# SoftStart_V2_0.net
KiCad netlist of a schematic drawn in EAGLE
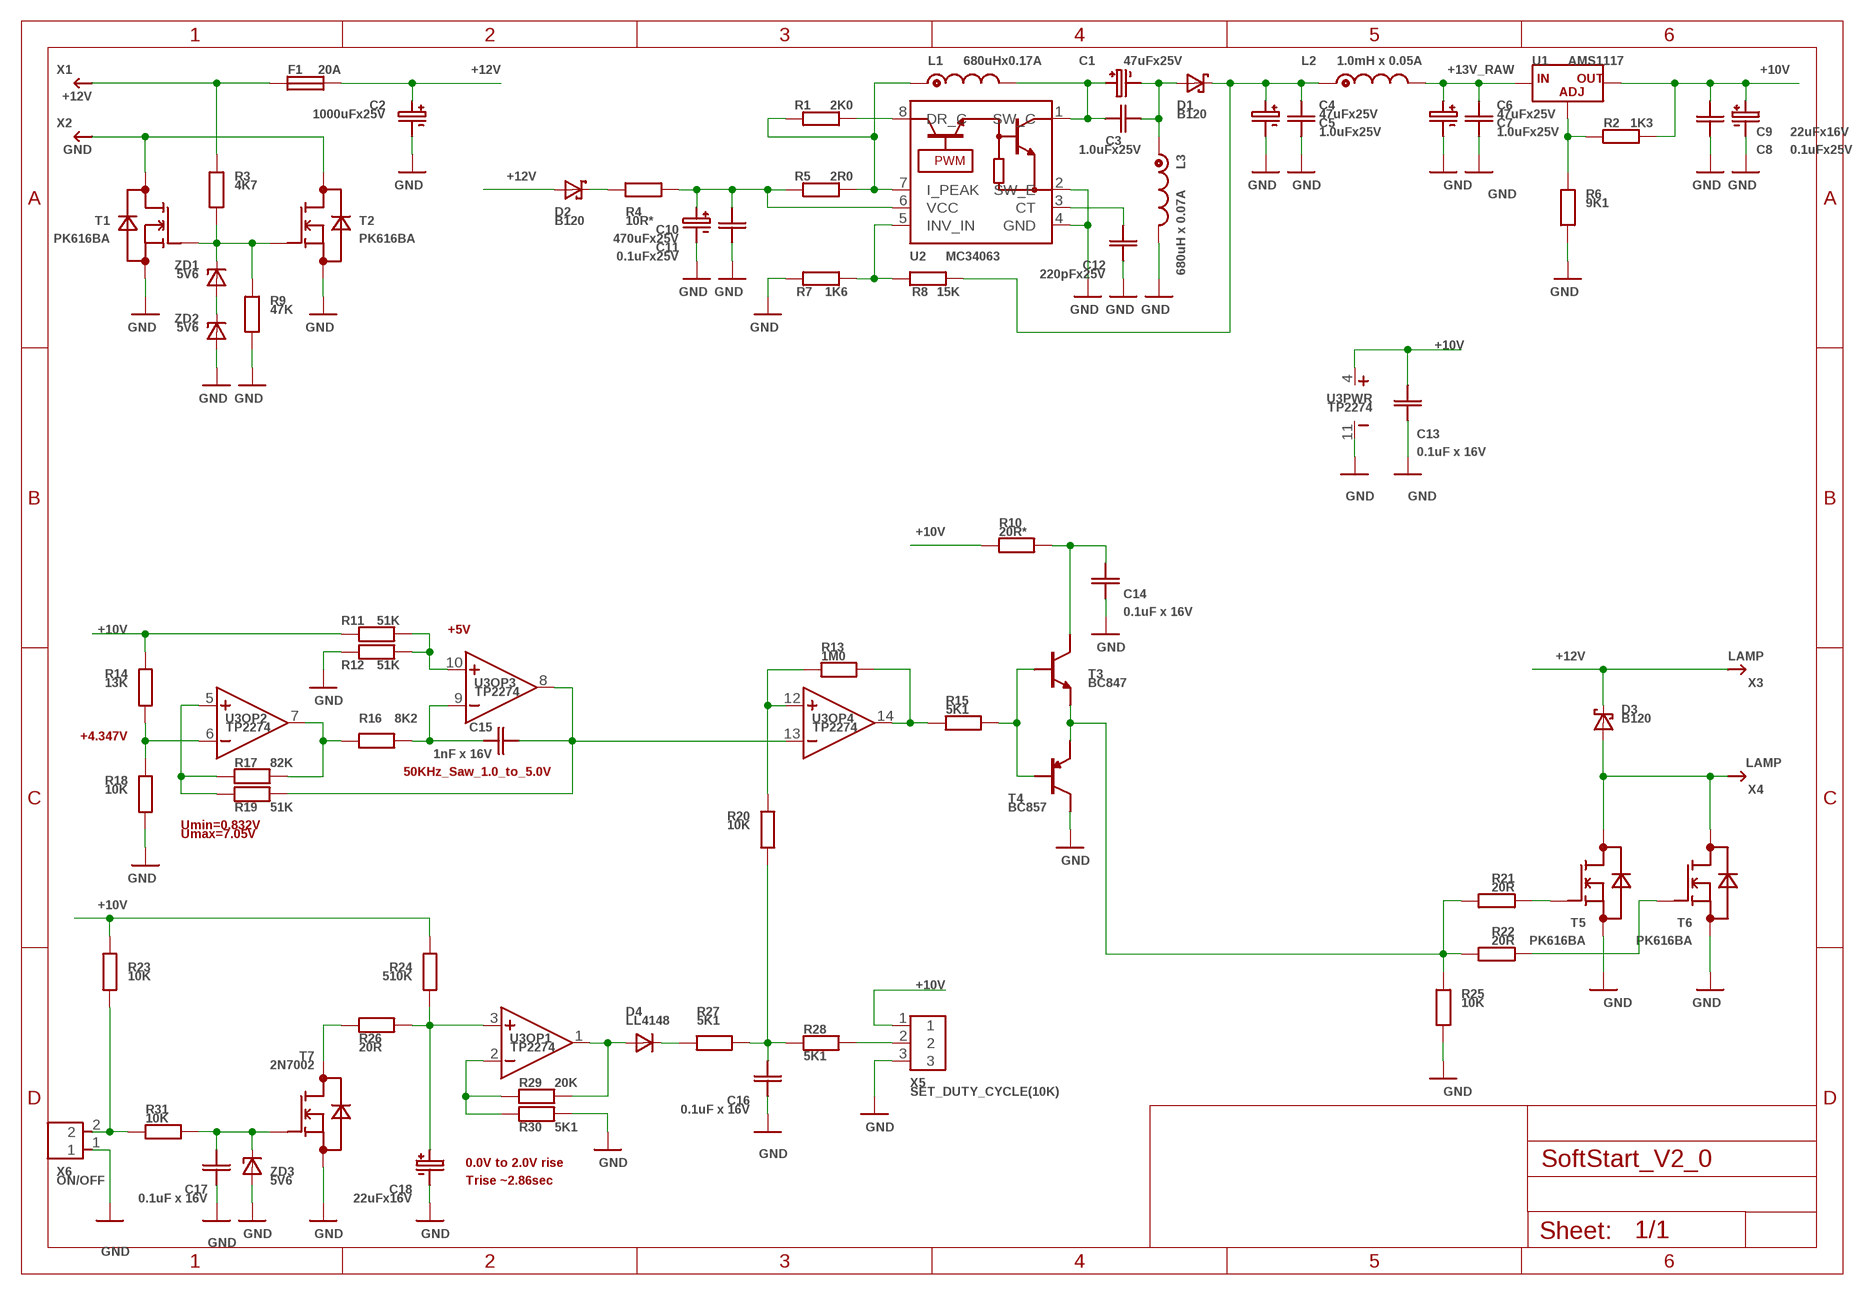
[diagram p0: schematic, sheet 1]

(export (version "E")
  (design (tool "Eeschema 10.0.6"))
  (components
    (comp (ref "C1")
      (value "47uFx25V")
      (footprint "eagle-import:CE_6.3MM")
      (libsource (lib "eagle-import") (part "CE6.3MM"))
    )
    (comp (ref "C2")
      (value "1000uFx25V")
      (footprint "eagle-import:CE_10MM")
      (libsource (lib "eagle-import") (part "CE10MM"))
    )
    (comp (ref "C3")
      (value "1.0uFx25V")
      (footprint "eagle-import:RSMD_1206")
      (libsource (lib "eagle-import") (part "CSMD_1206"))
    )
    (comp (ref "C4")
      (value "47uFx25V")
      (footprint "eagle-import:CE_6.3MM")
      (libsource (lib "eagle-import") (part "CE6.3MM"))
    )
    (comp (ref "C5")
      (value "1.0uFx25V")
      (footprint "eagle-import:RSMD_1206")
      (libsource (lib "eagle-import") (part "CSMD_1206"))
    )
    (comp (ref "C6")
      (value "47uFx25V")
      (footprint "eagle-import:CE_6.3MM")
      (libsource (lib "eagle-import") (part "CE6.3MM"))
    )
    (comp (ref "C7")
      (value "1.0uFx25V")
      (footprint "eagle-import:RSMD_1206")
      (libsource (lib "eagle-import") (part "CSMD_1206"))
    )
    (comp (ref "C8")
      (value "0.1uFx25V")
      (footprint "eagle-import:RSMD_0805")
      (libsource (lib "eagle-import") (part "CSMD_0805"))
    )
    (comp (ref "C9")
      (value "22uFx16V")
      (footprint "eagle-import:CE_6.3MM")
      (libsource (lib "eagle-import") (part "CE6.3MM"))
    )
    (comp (ref "C10")
      (value "470uFx25V")
      (footprint "eagle-import:CE_10MM")
      (libsource (lib "eagle-import") (part "CE10MM"))
    )
    (comp (ref "C11")
      (value "0.1uFx25V")
      (footprint "eagle-import:RSMD_1206")
      (libsource (lib "eagle-import") (part "CSMD_1206"))
    )
    (comp (ref "C12")
      (value "220pFx25V")
      (footprint "eagle-import:RSMD_0805")
      (libsource (lib "eagle-import") (part "CSMD_0805"))
    )
    (comp (ref "C13")
      (value "0.1uF x 16V")
      (footprint "eagle-import:RSMD_0805")
      (libsource (lib "eagle-import") (part "CSMD_0805"))
    )
    (comp (ref "C14")
      (value "0.1uF x 16V")
      (footprint "eagle-import:RSMD_0805")
      (libsource (lib "eagle-import") (part "CSMD_0805"))
    )
    (comp (ref "C15")
      (value "1nF x 16V")
      (footprint "eagle-import:RSMD_0805")
      (libsource (lib "eagle-import") (part "CSMD_0805"))
    )
    (comp (ref "C16")
      (value "0.1uF x 16V")
      (footprint "eagle-import:RSMD_0805")
      (libsource (lib "eagle-import") (part "CSMD_0805"))
    )
    (comp (ref "C17")
      (value "0.1uF x 16V")
      (footprint "eagle-import:RSMD_0805")
      (libsource (lib "eagle-import") (part "CSMD_0805"))
    )
    (comp (ref "C18")
      (value "22uFx16V")
      (footprint "eagle-import:CE_6.3MM")
      (libsource (lib "eagle-import") (part "CE6.3MM"))
    )
    (comp (ref "D1")
      (value "B120")
      (footprint "eagle-import:DO-214AC")
      (libsource (lib "eagle-import") (part "B120(DO-214AC)"))
    )
    (comp (ref "D2")
      (value "B120")
      (footprint "eagle-import:DO-214AC")
      (libsource (lib "eagle-import") (part "B120(DO-214AC)"))
    )
    (comp (ref "D3")
      (value "B120")
      (footprint "eagle-import:DO-214AC")
      (libsource (lib "eagle-import") (part "B120(DO-214AC)"))
    )
    (comp (ref "D4")
      (value "LL4148")
      (footprint "eagle-import:SOD-80")
      (libsource (lib "eagle-import") (part "LL4147SOD-80"))
    )
    (comp (ref "F1")
      (value "20A")
      (footprint "eagle-import:FUSE_AUTO_MINI_ON_TERMINALS")
      (libsource (lib "eagle-import") (part "FUSEAUTO_MINI_TERMINALS"))
    )
    (comp (ref "L1")
      (value "680uHx0.17A")
      (footprint "eagle-import:LCHB0608")
      (libsource (lib "eagle-import") (part "L(LCHB0608)"))
    )
    (comp (ref "L2")
      (value "1.0mH x 0.05A")
      (footprint "eagle-import:LCHB0608")
      (libsource (lib "eagle-import") (part "L(LCHB0608)"))
    )
    (comp (ref "L3")
      (value "680uH x 0.07A")
      (footprint "eagle-import:LCHB0608")
      (libsource (lib "eagle-import") (part "L(LCHB0608)"))
    )
    (comp (ref "R1")
      (value "2K0")
      (footprint "eagle-import:RSMD_0805")
      (libsource (lib "eagle-import") (part "RSMD_0805"))
    )
    (comp (ref "R2")
      (value "1K3")
      (footprint "eagle-import:RSMD_0805")
      (libsource (lib "eagle-import") (part "RSMD_0805"))
    )
    (comp (ref "R3")
      (value "4K7")
      (footprint "eagle-import:RSMD_0805")
      (libsource (lib "eagle-import") (part "RSMD_0805"))
    )
    (comp (ref "R4")
      (value "10R*")
      (footprint "eagle-import:RSMD_1206_BIG_GAP")
      (libsource (lib "eagle-import") (part "RSMD_1206_BIG_GAP"))
    )
    (comp (ref "R5")
      (value "2R0")
      (footprint "eagle-import:RSMD_1206_BIG_GAP")
      (libsource (lib "eagle-import") (part "RSMD_1206_BIG_GAP"))
    )
    (comp (ref "R6")
      (value "9K1")
      (footprint "eagle-import:RSMD_0805")
      (libsource (lib "eagle-import") (part "RSMD_0805"))
    )
    (comp (ref "R7")
      (value "1K6")
      (footprint "eagle-import:RSMD_0805")
      (libsource (lib "eagle-import") (part "RSMD_0805"))
    )
    (comp (ref "R8")
      (value "15K")
      (footprint "eagle-import:RSMD_0805")
      (libsource (lib "eagle-import") (part "RSMD_0805"))
    )
    (comp (ref "R9")
      (value "47K")
      (footprint "eagle-import:RSMD_0805")
      (libsource (lib "eagle-import") (part "RSMD_0805"))
    )
    (comp (ref "R10")
      (value "20R*")
      (footprint "eagle-import:RSMD_1206")
      (libsource (lib "eagle-import") (part "RSMD_1206"))
    )
    (comp (ref "R11")
      (value "51K")
      (footprint "eagle-import:RSMD_0805")
      (libsource (lib "eagle-import") (part "RSMD_0805"))
    )
    (comp (ref "R12")
      (value "51K")
      (footprint "eagle-import:RSMD_0805")
      (libsource (lib "eagle-import") (part "RSMD_0805"))
    )
    (comp (ref "R13")
      (value "1M0")
      (footprint "eagle-import:RSMD_0805")
      (libsource (lib "eagle-import") (part "RSMD_0805"))
    )
    (comp (ref "R14")
      (value "13K")
      (footprint "eagle-import:RSMD_0805")
      (libsource (lib "eagle-import") (part "RSMD_0805"))
    )
    (comp (ref "R15")
      (value "5K1")
      (footprint "eagle-import:RSMD_0805")
      (libsource (lib "eagle-import") (part "RSMD_0805"))
    )
    (comp (ref "R16")
      (value "8K2")
      (footprint "eagle-import:RSMD_0805")
      (libsource (lib "eagle-import") (part "RSMD_0805"))
    )
    (comp (ref "R17")
      (value "82K")
      (footprint "eagle-import:RSMD_0805")
      (libsource (lib "eagle-import") (part "RSMD_0805"))
    )
    (comp (ref "R18")
      (value "10K")
      (footprint "eagle-import:RSMD_0805")
      (libsource (lib "eagle-import") (part "RSMD_0805"))
    )
    (comp (ref "R19")
      (value "51K")
      (footprint "eagle-import:RSMD_0805")
      (libsource (lib "eagle-import") (part "RSMD_0805"))
    )
    (comp (ref "R20")
      (value "10K")
      (footprint "eagle-import:RSMD_1206_BIG_GAP")
      (libsource (lib "eagle-import") (part "RSMD_1206_BIG_GAP"))
    )
    (comp (ref "R21")
      (value "20R")
      (footprint "eagle-import:RSMD_0805")
      (libsource (lib "eagle-import") (part "RSMD_0805"))
    )
    (comp (ref "R22")
      (value "20R")
      (footprint "eagle-import:RSMD_0805")
      (libsource (lib "eagle-import") (part "RSMD_0805"))
    )
    (comp (ref "R23")
      (value "10K")
      (footprint "eagle-import:RSMD_0805")
      (libsource (lib "eagle-import") (part "RSMD_0805"))
    )
    (comp (ref "R24")
      (value "510K")
      (footprint "eagle-import:RSMD_0805")
      (libsource (lib "eagle-import") (part "RSMD_0805"))
    )
    (comp (ref "R25")
      (value "10K")
      (footprint "eagle-import:RSMD_0805")
      (libsource (lib "eagle-import") (part "RSMD_0805"))
    )
    (comp (ref "R26")
      (value "20R")
      (footprint "eagle-import:RSMD_0805")
      (libsource (lib "eagle-import") (part "RSMD_0805"))
    )
    (comp (ref "R27")
      (value "5K1")
      (footprint "eagle-import:RSMD_0805")
      (libsource (lib "eagle-import") (part "RSMD_0805"))
    )
    (comp (ref "R28")
      (value "5K1")
      (footprint "eagle-import:RSMD_0805")
      (libsource (lib "eagle-import") (part "RSMD_0805"))
    )
    (comp (ref "R29")
      (value "20K")
      (footprint "eagle-import:RSMD_0805")
      (libsource (lib "eagle-import") (part "RSMD_0805"))
    )
    (comp (ref "R30")
      (value "5K1")
      (footprint "eagle-import:RSMD_0805")
      (libsource (lib "eagle-import") (part "RSMD_0805"))
    )
    (comp (ref "R31")
      (value "10K")
      (footprint "eagle-import:RSMD_0805")
      (libsource (lib "eagle-import") (part "RSMD_0805"))
    )
    (comp (ref "T1")
      (value "PK616BA")
      (footprint "eagle-import:PDFN_5X6P")
      (libsource (lib "eagle-import") (part "PK616BA(PDFN_5X6P)"))
    )
    (comp (ref "T2")
      (value "PK616BA")
      (footprint "eagle-import:PDFN_5X6P")
      (libsource (lib "eagle-import") (part "PK616BA(PDFN_5X6P)"))
    )
    (comp (ref "T3")
      (value "BC847")
      (footprint "eagle-import:SOT23")
      (libsource (lib "eagle-import") (part "BC847SOT23"))
    )
    (comp (ref "T4")
      (value "BC857")
      (footprint "eagle-import:SOT23")
      (libsource (lib "eagle-import") (part "BC857SOT23"))
    )
    (comp (ref "T5")
      (value "PK616BA")
      (footprint "eagle-import:PDFN_5X6P")
      (libsource (lib "eagle-import") (part "PK616BA(PDFN_5X6P)"))
    )
    (comp (ref "T6")
      (value "PK616BA")
      (footprint "eagle-import:PDFN_5X6P")
      (libsource (lib "eagle-import") (part "PK616BA(PDFN_5X6P)"))
    )
    (comp (ref "T7")
      (value "2N7002")
      (footprint "eagle-import:SOT23")
      (libsource (lib "eagle-import") (part "2N7002SOT23"))
    )
    (comp (ref "U1")
      (value "AMS1117")
      (footprint "eagle-import:SOT223(WAVE_SOLDERING)")
      (libsource (lib "eagle-import") (part "AMS1117SOT223_WS"))
    )
    (comp (ref "U2")
      (value "MC34063")
      (footprint "eagle-import:SOIC8")
      (libsource (lib "eagle-import") (part "MC34063(SO-8)"))
    )
    (comp (ref "U3")
      (value "TP2274")
      (footprint "eagle-import:SOIC14")
      (libsource (lib "eagle-import") (part "LM324"))
    )
    (comp (ref "X1")
      (value "+12V")
      (footprint "eagle-import:RPI_6.3")
      (libsource (lib "eagle-import") (part "RPI_MALE6.3_TWO_HOLES"))
    )
    (comp (ref "X2")
      (value "GND")
      (footprint "eagle-import:RPI_6.3")
      (libsource (lib "eagle-import") (part "RPI_MALE6.3_TWO_HOLES"))
    )
    (comp (ref "X3")
      (value "LAMP")
      (footprint "eagle-import:RPI_6.3")
      (libsource (lib "eagle-import") (part "RPI_MALE6.3_TWO_HOLES"))
    )
    (comp (ref "X4")
      (value "LAMP")
      (footprint "eagle-import:RPI_6.3")
      (libsource (lib "eagle-import") (part "RPI_MALE6.3_TWO_HOLES"))
    )
    (comp (ref "X5")
      (value "SET_DUTY_CYCLE(10K)")
      (footprint "eagle-import:PIN3X1_2.54MM_WITH_CLAMP")
      (libsource (lib "eagle-import") (part "PIN1X3(2.54MM_WITH_CLAMP)"))
    )
    (comp (ref "X6")
      (value "ON/OFF")
      (footprint "eagle-import:PIN2X1_2.54_WITH_CLAMP")
      (libsource (lib "eagle-import") (part "PIN1X22.54MM_WITH_CLAMP"))
    )
    (comp (ref "ZD1")
      (value "5V6")
      (footprint "eagle-import:SOD-80")
      (libsource (lib "eagle-import") (part "ZENNER(SOD_80)"))
    )
    (comp (ref "ZD2")
      (value "5V6")
      (footprint "eagle-import:SOD-80")
      (libsource (lib "eagle-import") (part "ZENNER(SOD_80)"))
    )
    (comp (ref "ZD3")
      (value "5V6")
      (footprint "eagle-import:SOD-80")
      (libsource (lib "eagle-import") (part "ZENNER(SOD_80)"))
    )
  )
  (nets
    (net (code "1") (name "/+10V") (class "Default")
      (node (ref "C13") (pin "PAD_1") (pinfunction "PIN1_PAD_1") (pintype "bidirectional"))
      (node (ref "C8") (pin "PAD_1") (pinfunction "PIN1_PAD_1") (pintype "bidirectional"))
      (node (ref "C9") (pin "PLUS") (pinfunction "PLUS_PLUS") (pintype "bidirectional"))
      (node (ref "R10") (pin "PAD_0") (pinfunction "PIN0_PAD_0") (pintype "passive"))
      (node (ref "R11") (pin "PAD_1") (pinfunction "PIN1_PAD_1") (pintype "passive"))
      (node (ref "R14") (pin "PAD_1") (pinfunction "PIN1_PAD_1") (pintype "passive"))
      (node (ref "R2") (pin "PAD_0") (pinfunction "PIN0_PAD_0") (pintype "passive"))
      (node (ref "R23") (pin "PAD_1") (pinfunction "PIN1_PAD_1") (pintype "passive"))
      (node (ref "R24") (pin "PAD_1") (pinfunction "PIN1_PAD_1") (pintype "passive"))
      (node (ref "U1") (pin "2") (pinfunction "OUT_2") (pintype "output"))
      (node (ref "U1") (pin "4") (pinfunction "OUT_4") (pintype "output"))
      (node (ref "U3") (pin "4") (pinfunction "VCC_4") (pintype "power_in"))
      (node (ref "X5") (pin "1") (pinfunction "1_1") (pintype "passive"))
    )
    (net (code "2") (name "/+12V") (class "Default")
      (node (ref "C2") (pin "PLUS") (pinfunction "PLUS_PLUS") (pintype "bidirectional"))
      (node (ref "D2") (pin "ANODE") (pinfunction "ANODE_ANODE") (pintype "passive"))
      (node (ref "D3") (pin "CATHODE") (pinfunction "CATHODE_CATHODE") (pintype "passive"))
      (node (ref "F1") (pin "PAD0") (pinfunction "PIN0_PAD0") (pintype "passive"))
      (node (ref "X3") (pin "PAD1") (pinfunction "1_PAD1") (pintype "bidirectional"))
      (node (ref "X3") (pin "PAD2") (pinfunction "1_PAD2") (pintype "bidirectional"))
    )
    (net (code "3") (name "/+13V_RAW") (class "Default")
      (node (ref "C6") (pin "PLUS") (pinfunction "PLUS_PLUS") (pintype "bidirectional"))
      (node (ref "C7") (pin "PAD_0") (pinfunction "PIN0_PAD_0") (pintype "bidirectional"))
      (node (ref "L2") (pin "2") (pinfunction "END_2") (pintype "bidirectional"))
      (node (ref "U1") (pin "3") (pinfunction "IN_3") (pintype "input"))
    )
    (net (code "4") (name "GND") (class "Default")
      (node (ref "C10") (pin "MINUS") (pinfunction "MINUS_MINUS") (pintype "bidirectional"))
      (node (ref "C11") (pin "PAD_0") (pinfunction "PIN0_PAD_0") (pintype "bidirectional"))
      (node (ref "C12") (pin "PAD_0") (pinfunction "PIN0_PAD_0") (pintype "bidirectional"))
      (node (ref "C13") (pin "PAD_0") (pinfunction "PIN0_PAD_0") (pintype "bidirectional"))
      (node (ref "C14") (pin "PAD_0") (pinfunction "PIN0_PAD_0") (pintype "bidirectional"))
      (node (ref "C16") (pin "PAD_0") (pinfunction "PIN0_PAD_0") (pintype "bidirectional"))
      (node (ref "C17") (pin "PAD_0") (pinfunction "PIN0_PAD_0") (pintype "bidirectional"))
      (node (ref "C18") (pin "MINUS") (pinfunction "MINUS_MINUS") (pintype "bidirectional"))
      (node (ref "C2") (pin "MINUS") (pinfunction "MINUS_MINUS") (pintype "bidirectional"))
      (node (ref "C4") (pin "MINUS") (pinfunction "MINUS_MINUS") (pintype "bidirectional"))
      (node (ref "C5") (pin "PAD_1") (pinfunction "PIN1_PAD_1") (pintype "bidirectional"))
      (node (ref "C6") (pin "MINUS") (pinfunction "MINUS_MINUS") (pintype "bidirectional"))
      (node (ref "C7") (pin "PAD_1") (pinfunction "PIN1_PAD_1") (pintype "bidirectional"))
      (node (ref "C8") (pin "PAD_0") (pinfunction "PIN0_PAD_0") (pintype "bidirectional"))
      (node (ref "C9") (pin "MINUS") (pinfunction "MINUS_MINUS") (pintype "bidirectional"))
      (node (ref "L3") (pin "2") (pinfunction "END_2") (pintype "bidirectional"))
      (node (ref "R12") (pin "PAD_1") (pinfunction "PIN1_PAD_1") (pintype "passive"))
      (node (ref "R18") (pin "PAD_0") (pinfunction "PIN0_PAD_0") (pintype "passive"))
      (node (ref "R25") (pin "PAD_1") (pinfunction "PIN1_PAD_1") (pintype "passive"))
      (node (ref "R30") (pin "PAD_0") (pinfunction "PIN0_PAD_0") (pintype "passive"))
      (node (ref "R6") (pin "PAD_0") (pinfunction "PIN0_PAD_0") (pintype "passive"))
      (node (ref "R7") (pin "PAD_0") (pinfunction "PIN0_PAD_0") (pintype "passive"))
      (node (ref "R9") (pin "PAD_0") (pinfunction "PIN0_PAD_0") (pintype "passive"))
      (node (ref "T1") (pin "S1") (pinfunction "SOURCE_S1") (pintype "bidirectional"))
      (node (ref "T1") (pin "S2") (pinfunction "SOURCE_S2") (pintype "bidirectional"))
      (node (ref "T1") (pin "S3") (pinfunction "SOURCE_S3") (pintype "bidirectional"))
      (node (ref "T2") (pin "S1") (pinfunction "SOURCE_S1") (pintype "bidirectional"))
      (node (ref "T2") (pin "S2") (pinfunction "SOURCE_S2") (pintype "bidirectional"))
      (node (ref "T2") (pin "S3") (pinfunction "SOURCE_S3") (pintype "bidirectional"))
      (node (ref "T4") (pin "3") (pinfunction "C_3") (pintype "bidirectional"))
      (node (ref "T5") (pin "S1") (pinfunction "SOURCE_S1") (pintype "bidirectional"))
      (node (ref "T5") (pin "S2") (pinfunction "SOURCE_S2") (pintype "bidirectional"))
      (node (ref "T5") (pin "S3") (pinfunction "SOURCE_S3") (pintype "bidirectional"))
      (node (ref "T6") (pin "S1") (pinfunction "SOURCE_S1") (pintype "bidirectional"))
      (node (ref "T6") (pin "S2") (pinfunction "SOURCE_S2") (pintype "bidirectional"))
      (node (ref "T6") (pin "S3") (pinfunction "SOURCE_S3") (pintype "bidirectional"))
      (node (ref "T7") (pin "2") (pinfunction "SOURCE_2") (pintype "bidirectional"))
      (node (ref "U2") (pin "2") (pinfunction "SW_E_2") (pintype "bidirectional"))
      (node (ref "U2") (pin "4") (pinfunction "GND_4") (pintype "bidirectional"))
      (node (ref "U3") (pin "11") (pinfunction "GND_11") (pintype "power_in"))
      (node (ref "X5") (pin "3") (pinfunction "3_3") (pintype "passive"))
      (node (ref "X6") (pin "1") (pinfunction "1_1") (pintype "bidirectional"))
      (node (ref "ZD2") (pin "ANODE") (pinfunction "ANODE_ANODE") (pintype "passive"))
      (node (ref "ZD3") (pin "ANODE") (pinfunction "ANODE_ANODE") (pintype "passive"))
    )
    (net (code "5") (name "Net-(C3-PIN0)") (class "Default")
      (node (ref "C1") (pin "MINUS") (pinfunction "MINUS_MINUS") (pintype "bidirectional"))
      (node (ref "C3") (pin "PAD_0") (pinfunction "PIN0_PAD_0") (pintype "bidirectional"))
      (node (ref "D1") (pin "ANODE") (pinfunction "ANODE_ANODE") (pintype "passive"))
      (node (ref "L3") (pin "1") (pinfunction "START_1") (pintype "bidirectional"))
    )
    (net (code "6") (name "Net-(C3-PIN1)") (class "Default")
      (node (ref "C1") (pin "PLUS") (pinfunction "PLUS_PLUS") (pintype "bidirectional"))
      (node (ref "C3") (pin "PAD_1") (pinfunction "PIN1_PAD_1") (pintype "bidirectional"))
      (node (ref "L1") (pin "2") (pinfunction "END_2") (pintype "bidirectional"))
      (node (ref "U2") (pin "1") (pinfunction "SW_C_1") (pintype "bidirectional"))
    )
    (net (code "7") (name "Net-(C5-PIN0)") (class "Default")
      (node (ref "C4") (pin "PLUS") (pinfunction "PLUS_PLUS") (pintype "bidirectional"))
      (node (ref "C5") (pin "PAD_0") (pinfunction "PIN0_PAD_0") (pintype "bidirectional"))
      (node (ref "D1") (pin "CATHODE") (pinfunction "CATHODE_CATHODE") (pintype "passive"))
      (node (ref "L2") (pin "1") (pinfunction "START_1") (pintype "bidirectional"))
      (node (ref "R8") (pin "PAD_1") (pinfunction "PIN1_PAD_1") (pintype "passive"))
    )
    (net (code "8") (name "Net-(C11-PIN1)") (class "Default")
      (node (ref "C10") (pin "PLUS") (pinfunction "PLUS_PLUS") (pintype "bidirectional"))
      (node (ref "C11") (pin "PAD_1") (pinfunction "PIN1_PAD_1") (pintype "bidirectional"))
      (node (ref "R4") (pin "PAD_0") (pinfunction "PIN0_PAD_0") (pintype "passive"))
      (node (ref "R5") (pin "PAD_1") (pinfunction "PIN1_PAD_1") (pintype "passive"))
      (node (ref "U2") (pin "6") (pinfunction "VCC_6") (pintype "bidirectional"))
    )
    (net (code "9") (name "Net-(C12-PIN1)") (class "Default")
      (node (ref "C12") (pin "PAD_1") (pinfunction "PIN1_PAD_1") (pintype "bidirectional"))
      (node (ref "U2") (pin "3") (pinfunction "CT_3") (pintype "bidirectional"))
    )
    (net (code "10") (name "Net-(C14-PIN1)") (class "Default")
      (node (ref "C14") (pin "PAD_1") (pinfunction "PIN1_PAD_1") (pintype "bidirectional"))
      (node (ref "R10") (pin "PAD_1") (pinfunction "PIN1_PAD_1") (pintype "passive"))
      (node (ref "T3") (pin "3") (pinfunction "C_3") (pintype "bidirectional"))
    )
    (net (code "11") (name "Net-(C15-PIN0)") (class "Default")
      (node (ref "C15") (pin "PAD_0") (pinfunction "PIN0_PAD_0") (pintype "bidirectional"))
      (node (ref "R19") (pin "PAD_1") (pinfunction "PIN1_PAD_1") (pintype "passive"))
      (node (ref "U3") (pin "13") (pinfunction "IN-_13") (pintype "input"))
      (node (ref "U3") (pin "8") (pinfunction "OUT_8") (pintype "output"))
    )
    (net (code "12") (name "Net-(C15-PIN1)") (class "Default")
      (node (ref "C15") (pin "PAD_1") (pinfunction "PIN1_PAD_1") (pintype "bidirectional"))
      (node (ref "R16") (pin "PAD_1") (pinfunction "PIN1_PAD_1") (pintype "passive"))
      (node (ref "U3") (pin "9") (pinfunction "IN-_9") (pintype "input"))
    )
    (net (code "13") (name "Net-(C16-PIN1)") (class "Default")
      (node (ref "C16") (pin "PAD_1") (pinfunction "PIN1_PAD_1") (pintype "bidirectional"))
      (node (ref "R20") (pin "PAD_0") (pinfunction "PIN0_PAD_0") (pintype "passive"))
      (node (ref "R27") (pin "PAD_1") (pinfunction "PIN1_PAD_1") (pintype "passive"))
      (node (ref "R28") (pin "PAD_1") (pinfunction "PIN1_PAD_1") (pintype "passive"))
    )
    (net (code "14") (name "Net-(C17-PIN1)") (class "Default")
      (node (ref "C17") (pin "PAD_1") (pinfunction "PIN1_PAD_1") (pintype "bidirectional"))
      (node (ref "R31") (pin "PAD_0") (pinfunction "PIN0_PAD_0") (pintype "passive"))
      (node (ref "T7") (pin "1") (pinfunction "GATE_1") (pintype "bidirectional"))
      (node (ref "ZD3") (pin "CATHODE") (pinfunction "CATHODE_CATHODE") (pintype "passive"))
    )
    (net (code "15") (name "Net-(D3-PadANODE)") (class "Default")
      (node (ref "D3") (pin "ANODE") (pinfunction "ANODE_ANODE") (pintype "passive"))
      (node (ref "T5") (pin "D") (pinfunction "DRAIN_D") (pintype "bidirectional"))
      (node (ref "T5") (pin "D1") (pinfunction "DRAIN_D1") (pintype "bidirectional"))
      (node (ref "T5") (pin "D2") (pinfunction "DRAIN_D2") (pintype "bidirectional"))
      (node (ref "T5") (pin "D3") (pinfunction "DRAIN_D3") (pintype "bidirectional"))
      (node (ref "T5") (pin "D4") (pinfunction "DRAIN_D4") (pintype "bidirectional"))
      (node (ref "T6") (pin "D") (pinfunction "DRAIN_D") (pintype "bidirectional"))
      (node (ref "T6") (pin "D1") (pinfunction "DRAIN_D1") (pintype "bidirectional"))
      (node (ref "T6") (pin "D2") (pinfunction "DRAIN_D2") (pintype "bidirectional"))
      (node (ref "T6") (pin "D3") (pinfunction "DRAIN_D3") (pintype "bidirectional"))
      (node (ref "T6") (pin "D4") (pinfunction "DRAIN_D4") (pintype "bidirectional"))
      (node (ref "X4") (pin "PAD1") (pinfunction "1_PAD1") (pintype "bidirectional"))
      (node (ref "X4") (pin "PAD2") (pinfunction "1_PAD2") (pintype "bidirectional"))
    )
    (net (code "16") (name "Net-(F1-PIN1)") (class "Default")
      (node (ref "F1") (pin "PAD1") (pinfunction "PIN1_PAD1") (pintype "passive"))
      (node (ref "R3") (pin "PAD_1") (pinfunction "PIN1_PAD_1") (pintype "passive"))
      (node (ref "X1") (pin "PAD1") (pinfunction "1_PAD1") (pintype "bidirectional"))
      (node (ref "X1") (pin "PAD2") (pinfunction "1_PAD2") (pintype "bidirectional"))
    )
    (net (code "17") (name "Net-(L1-START)") (class "Default")
      (node (ref "L1") (pin "1") (pinfunction "START_1") (pintype "bidirectional"))
      (node (ref "R1") (pin "PAD_1") (pinfunction "PIN1_PAD_1") (pintype "passive"))
      (node (ref "R5") (pin "PAD_0") (pinfunction "PIN0_PAD_0") (pintype "passive"))
      (node (ref "U2") (pin "7") (pinfunction "I_PEAK_7") (pintype "bidirectional"))
    )
    (net (code "18") (name "Net-(R1-PIN0)") (class "Default")
      (node (ref "R1") (pin "PAD_0") (pinfunction "PIN0_PAD_0") (pintype "passive"))
      (node (ref "U2") (pin "8") (pinfunction "DR_C_8") (pintype "bidirectional"))
    )
    (net (code "19") (name "Net-(R2-PIN1)") (class "Default")
      (node (ref "R2") (pin "PAD_1") (pinfunction "PIN1_PAD_1") (pintype "passive"))
      (node (ref "R6") (pin "PAD_1") (pinfunction "PIN1_PAD_1") (pintype "passive"))
      (node (ref "U1") (pin "1") (pinfunction "ADJ_1") (pintype "input"))
    )
    (net (code "20") (name "Net-(R3-PIN0)") (class "Default")
      (node (ref "R3") (pin "PAD_0") (pinfunction "PIN0_PAD_0") (pintype "passive"))
      (node (ref "R9") (pin "PAD_1") (pinfunction "PIN1_PAD_1") (pintype "passive"))
      (node (ref "T1") (pin "G") (pinfunction "GATE_G") (pintype "bidirectional"))
      (node (ref "T2") (pin "G") (pinfunction "GATE_G") (pintype "bidirectional"))
      (node (ref "ZD1") (pin "CATHODE") (pinfunction "CATHODE_CATHODE") (pintype "passive"))
    )
    (net (code "21") (name "Net-(R4-PIN1)") (class "Default")
      (node (ref "D2") (pin "CATHODE") (pinfunction "CATHODE_CATHODE") (pintype "passive"))
      (node (ref "R4") (pin "PAD_1") (pinfunction "PIN1_PAD_1") (pintype "passive"))
    )
    (net (code "22") (name "Net-(R7-PIN1)") (class "Default")
      (node (ref "R7") (pin "PAD_1") (pinfunction "PIN1_PAD_1") (pintype "passive"))
      (node (ref "R8") (pin "PAD_0") (pinfunction "PIN0_PAD_0") (pintype "passive"))
      (node (ref "U2") (pin "5") (pinfunction "INV_IN_5") (pintype "bidirectional"))
    )
    (net (code "23") (name "Net-(R11-PIN0)") (class "Default")
      (node (ref "R11") (pin "PAD_0") (pinfunction "PIN0_PAD_0") (pintype "passive"))
      (node (ref "R12") (pin "PAD_0") (pinfunction "PIN0_PAD_0") (pintype "passive"))
      (node (ref "U3") (pin "10") (pinfunction "IN+_10") (pintype "input"))
    )
    (net (code "24") (name "Net-(R13-PIN0)") (class "Default")
      (node (ref "R13") (pin "PAD_0") (pinfunction "PIN0_PAD_0") (pintype "passive"))
      (node (ref "R20") (pin "PAD_1") (pinfunction "PIN1_PAD_1") (pintype "passive"))
      (node (ref "U3") (pin "12") (pinfunction "IN+_12") (pintype "input"))
    )
    (net (code "25") (name "Net-(R13-PIN1)") (class "Default")
      (node (ref "R13") (pin "PAD_1") (pinfunction "PIN1_PAD_1") (pintype "passive"))
      (node (ref "R15") (pin "PAD_0") (pinfunction "PIN0_PAD_0") (pintype "passive"))
      (node (ref "U3") (pin "14") (pinfunction "OUT_14") (pintype "output"))
    )
    (net (code "26") (name "Net-(R14-PIN0)") (class "Default")
      (node (ref "R14") (pin "PAD_0") (pinfunction "PIN0_PAD_0") (pintype "passive"))
      (node (ref "R18") (pin "PAD_1") (pinfunction "PIN1_PAD_1") (pintype "passive"))
      (node (ref "U3") (pin "6") (pinfunction "IN-_6") (pintype "input"))
    )
    (net (code "27") (name "Net-(R15-PIN1)") (class "Default")
      (node (ref "R15") (pin "PAD_1") (pinfunction "PIN1_PAD_1") (pintype "passive"))
      (node (ref "T3") (pin "1") (pinfunction "B_1") (pintype "bidirectional"))
      (node (ref "T4") (pin "1") (pinfunction "B_1") (pintype "bidirectional"))
    )
    (net (code "28") (name "Net-(R16-PIN0)") (class "Default")
      (node (ref "R16") (pin "PAD_0") (pinfunction "PIN0_PAD_0") (pintype "passive"))
      (node (ref "R17") (pin "PAD_1") (pinfunction "PIN1_PAD_1") (pintype "passive"))
      (node (ref "U3") (pin "7") (pinfunction "OUT_7") (pintype "output"))
    )
    (net (code "29") (name "Net-(R17-PIN0)") (class "Default")
      (node (ref "R17") (pin "PAD_0") (pinfunction "PIN0_PAD_0") (pintype "passive"))
      (node (ref "R19") (pin "PAD_0") (pinfunction "PIN0_PAD_0") (pintype "passive"))
      (node (ref "U3") (pin "5") (pinfunction "IN+_5") (pintype "input"))
    )
    (net (code "30") (name "Net-(R21-PIN0)") (class "Default")
      (node (ref "R21") (pin "PAD_0") (pinfunction "PIN0_PAD_0") (pintype "passive"))
      (node (ref "T5") (pin "G") (pinfunction "GATE_G") (pintype "bidirectional"))
    )
    (net (code "31") (name "Net-(R21-PIN1)") (class "Default")
      (node (ref "R21") (pin "PAD_1") (pinfunction "PIN1_PAD_1") (pintype "passive"))
      (node (ref "R22") (pin "PAD_1") (pinfunction "PIN1_PAD_1") (pintype "passive"))
      (node (ref "R25") (pin "PAD_0") (pinfunction "PIN0_PAD_0") (pintype "passive"))
      (node (ref "T3") (pin "2") (pinfunction "E_2") (pintype "bidirectional"))
      (node (ref "T4") (pin "2") (pinfunction "E_2") (pintype "bidirectional"))
    )
    (net (code "32") (name "Net-(R22-PIN0)") (class "Default")
      (node (ref "R22") (pin "PAD_0") (pinfunction "PIN0_PAD_0") (pintype "passive"))
      (node (ref "T6") (pin "G") (pinfunction "GATE_G") (pintype "bidirectional"))
    )
    (net (code "33") (name "Net-(R23-PIN0)") (class "Default")
      (node (ref "R23") (pin "PAD_0") (pinfunction "PIN0_PAD_0") (pintype "passive"))
      (node (ref "R31") (pin "PAD_1") (pinfunction "PIN1_PAD_1") (pintype "passive"))
      (node (ref "X6") (pin "2") (pinfunction "2_2") (pintype "bidirectional"))
    )
    (net (code "34") (name "Net-(R24-PIN0)") (class "Default")
      (node (ref "C18") (pin "PLUS") (pinfunction "PLUS_PLUS") (pintype "bidirectional"))
      (node (ref "R24") (pin "PAD_0") (pinfunction "PIN0_PAD_0") (pintype "passive"))
      (node (ref "R26") (pin "PAD_1") (pinfunction "PIN1_PAD_1") (pintype "passive"))
      (node (ref "U3") (pin "3") (pinfunction "IN+_3") (pintype "input"))
    )
    (net (code "35") (name "Net-(R26-PIN0)") (class "Default")
      (node (ref "R26") (pin "PAD_0") (pinfunction "PIN0_PAD_0") (pintype "passive"))
      (node (ref "T7") (pin "3") (pinfunction "DRAIN_3") (pintype "bidirectional"))
    )
    (net (code "36") (name "Net-(R27-PIN0)") (class "Default")
      (node (ref "D4") (pin "CATHODE") (pinfunction "CATHODE_CATHODE") (pintype "passive"))
      (node (ref "R27") (pin "PAD_0") (pinfunction "PIN0_PAD_0") (pintype "passive"))
    )
    (net (code "37") (name "Net-(R28-PIN0)") (class "Default")
      (node (ref "R28") (pin "PAD_0") (pinfunction "PIN0_PAD_0") (pintype "passive"))
      (node (ref "X5") (pin "2") (pinfunction "2_2") (pintype "passive"))
    )
    (net (code "38") (name "Net-(R29-PIN0)") (class "Default")
      (node (ref "D4") (pin "ANODE") (pinfunction "ANODE_ANODE") (pintype "passive"))
      (node (ref "R29") (pin "PAD_0") (pinfunction "PIN0_PAD_0") (pintype "passive"))
      (node (ref "U3") (pin "1") (pinfunction "OUT_1") (pintype "output"))
    )
    (net (code "39") (name "Net-(R29-PIN1)") (class "Default")
      (node (ref "R29") (pin "PAD_1") (pinfunction "PIN1_PAD_1") (pintype "passive"))
      (node (ref "R30") (pin "PAD_1") (pinfunction "PIN1_PAD_1") (pintype "passive"))
      (node (ref "U3") (pin "2") (pinfunction "IN-_2") (pintype "input"))
    )
    (net (code "40") (name "Net-(T1-DRAIN-PadD)") (class "Default")
      (node (ref "T1") (pin "D") (pinfunction "DRAIN_D") (pintype "bidirectional"))
      (node (ref "T1") (pin "D1") (pinfunction "DRAIN_D1") (pintype "bidirectional"))
      (node (ref "T1") (pin "D2") (pinfunction "DRAIN_D2") (pintype "bidirectional"))
      (node (ref "T1") (pin "D3") (pinfunction "DRAIN_D3") (pintype "bidirectional"))
      (node (ref "T1") (pin "D4") (pinfunction "DRAIN_D4") (pintype "bidirectional"))
      (node (ref "T2") (pin "D") (pinfunction "DRAIN_D") (pintype "bidirectional"))
      (node (ref "T2") (pin "D1") (pinfunction "DRAIN_D1") (pintype "bidirectional"))
      (node (ref "T2") (pin "D2") (pinfunction "DRAIN_D2") (pintype "bidirectional"))
      (node (ref "T2") (pin "D3") (pinfunction "DRAIN_D3") (pintype "bidirectional"))
      (node (ref "T2") (pin "D4") (pinfunction "DRAIN_D4") (pintype "bidirectional"))
      (node (ref "X2") (pin "PAD1") (pinfunction "1_PAD1") (pintype "bidirectional"))
      (node (ref "X2") (pin "PAD2") (pinfunction "1_PAD2") (pintype "bidirectional"))
    )
    (net (code "41") (name "Net-(ZD1-PadANODE)") (class "Default")
      (node (ref "ZD1") (pin "ANODE") (pinfunction "ANODE_ANODE") (pintype "passive"))
      (node (ref "ZD2") (pin "CATHODE") (pinfunction "CATHODE_CATHODE") (pintype "passive"))
    )
  )
)
